# DAC_ADC_External.net
KiCad netlist of a schematic drawn in Altium Designer
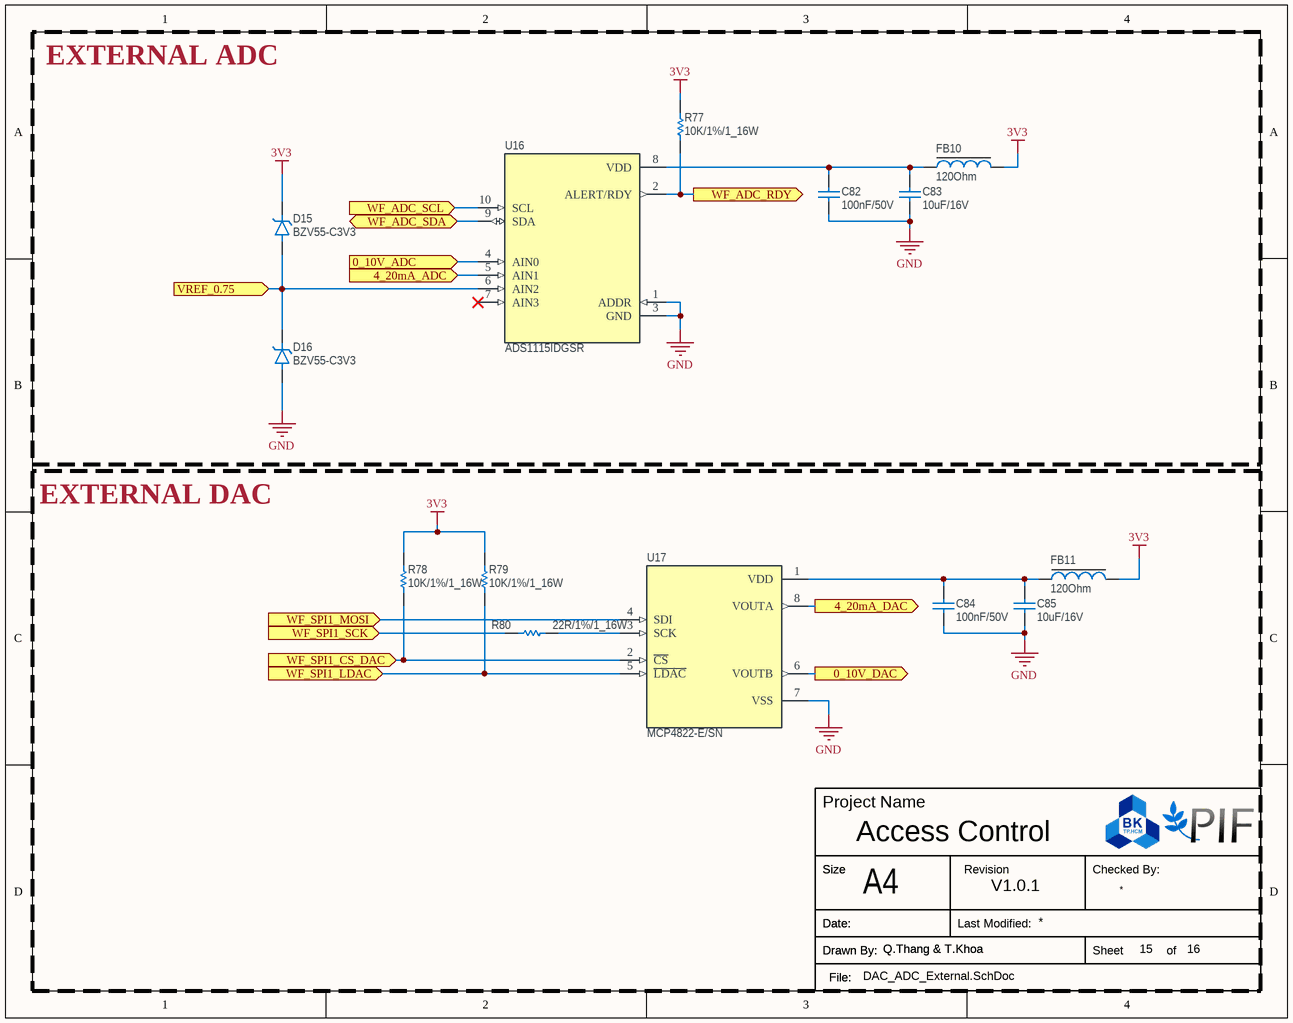
[diagram p0: DAC_ADC_External.SchDoc]

(export (version "E")
  (design (tool "Eeschema 10.0.6"))
  (components
    (comp (ref "C82")
      (value "100nF/50V")
      (footprint "CAP_0603")
      (description "CAP, size 0603, 100nF, 50V")
      (fields (field (name "SUPPLY PART NUMBER") "Tụ Gốm 0603 100nF (0.1uF) 50V"))
      (libsource (lib "BluetoothTracking") (part "Ceramic_Cap_100nF_50V_0603"))
    )
    (comp (ref "C83")
      (value "10uF/16V")
      (footprint "CAP_0603")
      (description "CAP, size 0603, 10uF, 16V")
      (fields (field (name "SUPPLY PART NUMBER") "Tụ Gốm 0603 10uF 16V"))
      (libsource (lib "BluetoothTracking") (part "Ceramic_Cap_10uF_16V_0603"))
    )
    (comp (ref "C84")
      (value "100nF/50V")
      (footprint "CAP_0603")
      (description "CAP, size 0603, 100nF, 50V")
      (fields (field (name "SUPPLY PART NUMBER") "Tụ Gốm 0603 100nF (0.1uF) 50V"))
      (libsource (lib "BluetoothTracking") (part "Ceramic_Cap_100nF_50V_0603"))
    )
    (comp (ref "C85")
      (value "10uF/16V")
      (footprint "CAP_0603")
      (description "CAP, size 0603, 10uF, 16V")
      (fields (field (name "SUPPLY PART NUMBER") "Tụ Gốm 0603 10uF 16V"))
      (libsource (lib "BluetoothTracking") (part "Ceramic_Cap_10uF_16V_0603"))
    )
    (comp (ref "D15")
      (value "BZV55-C3V3")
      (footprint "SOD-80")
      (description "DIODE ZENER 3.3V 500 mW")
      (libsource (lib "BluetoothTracking") (part "Diode_BZV55C3V3"))
    )
    (comp (ref "D16")
      (value "BZV55-C3V3")
      (footprint "SOD-80")
      (description "DIODE ZENER 3.3V 500 mW")
      (libsource (lib "BluetoothTracking") (part "Diode_BZV55C3V3"))
    )
    (comp (ref "FB10")
      (value "120Ohm")
      (footprint "Ferrite_Bead_0805")
      (description "Ferrite Bead, size 0805, 120Ohm, 2A")
      (fields (field (name "SUPPLY PART NUMBER") "CBW201209U121T Ferrite Beads 2A 120 Ohm 0805"))
      (libsource (lib "BluetoothTracking") (part "Ferrite_Bead_120Ohm_2A_0805"))
    )
    (comp (ref "FB11")
      (value "120Ohm")
      (footprint "Ferrite_Bead_0805")
      (description "Ferrite Bead, size 0805, 120Ohm, 2A")
      (fields (field (name "SUPPLY PART NUMBER") "CBW201209U121T Ferrite Beads 2A 120 Ohm 0805"))
      (libsource (lib "BluetoothTracking") (part "Ferrite_Bead_120Ohm_2A_0805"))
    )
    (comp (ref "R77")
      (value "10K/1%/1_16W")
      (footprint "RESISTOR_0402")
      (description "Resistor 0402 10KOhm 1% 1_16W")
      (fields (field (name "SUPPLY PART NUMBER") "Điện Trở 10 KOhm 0402 1%"))
      (libsource (lib "BluetoothTracking") (part "Res_10K_0402_1%"))
    )
    (comp (ref "R78")
      (value "10K/1%/1_16W")
      (footprint "RESISTOR_0402")
      (description "Resistor 0402 10KOhm 1% 1_16W")
      (fields (field (name "SUPPLY PART NUMBER") "Điện Trở 10 KOhm 0402 1%"))
      (libsource (lib "BluetoothTracking") (part "Res_10K_0402_1%"))
    )
    (comp (ref "R79")
      (value "10K/1%/1_16W")
      (footprint "RESISTOR_0402")
      (description "Resistor 0402 10KOhm 1% 1_16W")
      (fields (field (name "SUPPLY PART NUMBER") "Điện Trở 10 KOhm 0402 1%"))
      (libsource (lib "BluetoothTracking") (part "Res_10K_0402_1%"))
    )
    (comp (ref "R80")
      (value "22R/1%/1_16W")
      (footprint "RESISTOR_0402")
      (description "Resistor 0402 22 Ohm 1% 1_16W")
      (libsource (lib "BluetoothTracking") (part "Res_22R_0402_1%"))
    )
    (comp (ref "U16")
      (value "ADS1115IDGSR")
      (footprint "VSSOP-10")
      (fields (field (name "SUPPLY PART NUMBER") "ADS1115IDGSR IC ADC 16-Bit Sigma-Delta 10-VSSOP"))
      (libsource (lib "BluetoothTracking") (part "ADS1115IDGSR"))
    )
    (comp (ref "U17")
      (value "MCP4822-E/SN")
      (footprint "SOIC-8")
      (description "12 Bit Digital to Analog Converter 2 8-SOIC")
      (fields (field (name "SUPPLY PART NUMBER") "MCP4822-E/SN SOIC-8 DAC 12Bit Chính Hãng Microchip"))
      (libsource (lib "BluetoothTracking") (part "MCP4822-E/SN"))
    )
  )
  (nets
    (net (code "1") (name "/0_10V_ADC") (class "Default")
      (node (ref "U16") (pin "4") (pinfunction "AIN0_4") (pintype "input"))
    )
    (net (code "2") (name "/0_10V_DAC") (class "Default")
      (node (ref "U17") (pin "6") (pinfunction "VOUTB_6") (pintype "output"))
    )
    (net (code "3") (name "/4_20mA_ADC") (class "Default")
      (node (ref "U16") (pin "5") (pinfunction "AIN1_5") (pintype "input"))
    )
    (net (code "4") (name "/4_20mA_DAC") (class "Default")
      (node (ref "U17") (pin "8") (pinfunction "VOUTA_8") (pintype "output"))
    )
    (net (code "5") (name "/VREF_0.75") (class "Default")
      (node (ref "D15") (pin "A") (pinfunction "A_A") (pintype "passive"))
      (node (ref "D16") (pin "C") (pinfunction "C_C") (pintype "passive"))
      (node (ref "U16") (pin "6") (pinfunction "AIN2_6") (pintype "input"))
    )
    (net (code "6") (name "/WF_ADC_RDY") (class "Default")
      (node (ref "R77") (pin "1") (pinfunction "1_1") (pintype "passive"))
      (node (ref "U16") (pin "2") (pinfunction "ALERT/RDY_2") (pintype "output"))
    )
    (net (code "7") (name "/WF_ADC_SCL") (class "Default")
      (node (ref "U16") (pin "10") (pinfunction "SCL_10") (pintype "input"))
    )
    (net (code "8") (name "/WF_ADC_SDA") (class "Default")
      (node (ref "U16") (pin "9") (pinfunction "SDA_9") (pintype "bidirectional"))
    )
    (net (code "9") (name "/WF_SPI1_CS_DAC") (class "Default")
      (node (ref "R78") (pin "1") (pinfunction "1_1") (pintype "passive"))
      (node (ref "U17") (pin "2") (pinfunction "~{CS}_2") (pintype "input"))
    )
    (net (code "10") (name "/WF_SPI1_LDAC") (class "Default")
      (node (ref "R79") (pin "1") (pinfunction "1_1") (pintype "passive"))
      (node (ref "U17") (pin "5") (pinfunction "~{LDAC}_5") (pintype "input"))
    )
    (net (code "11") (name "/WF_SPI1_MOSI") (class "Default")
      (node (ref "U17") (pin "4") (pinfunction "SDI_4") (pintype "input"))
    )
    (net (code "12") (name "/WF_SPI1_SCK") (class "Default")
      (node (ref "R80") (pin "1") (pinfunction "1_1") (pintype "passive"))
    )
    (net (code "13") (name "3V3") (class "Default")
      (node (ref "D15") (pin "C") (pinfunction "C_C") (pintype "passive"))
      (node (ref "FB10") (pin "2") (pinfunction "2_2") (pintype "passive"))
      (node (ref "FB11") (pin "2") (pinfunction "2_2") (pintype "passive"))
      (node (ref "R77") (pin "2") (pinfunction "2_2") (pintype "passive"))
      (node (ref "R78") (pin "2") (pinfunction "2_2") (pintype "passive"))
      (node (ref "R79") (pin "2") (pinfunction "2_2") (pintype "passive"))
    )
    (net (code "14") (name "GND") (class "Default")
      (node (ref "C82") (pin "1") (pinfunction "1_1") (pintype "passive"))
      (node (ref "C83") (pin "1") (pinfunction "1_1") (pintype "passive"))
      (node (ref "C84") (pin "1") (pinfunction "1_1") (pintype "passive"))
      (node (ref "C85") (pin "1") (pinfunction "1_1") (pintype "passive"))
      (node (ref "D16") (pin "A") (pinfunction "A_A") (pintype "passive"))
      (node (ref "U16") (pin "1") (pinfunction "ADDR_1") (pintype "input"))
      (node (ref "U16") (pin "3") (pinfunction "GND_3") (pintype "power_in"))
      (node (ref "U17") (pin "7") (pinfunction "VSS_7") (pintype "power_in"))
    )
    (net (code "15") (name "Net-(U16-VDD)") (class "Default")
      (node (ref "C82") (pin "2") (pinfunction "2_2") (pintype "passive"))
      (node (ref "C83") (pin "2") (pinfunction "2_2") (pintype "passive"))
      (node (ref "FB10") (pin "1") (pinfunction "1_1") (pintype "passive"))
      (node (ref "U16") (pin "8") (pinfunction "VDD_8") (pintype "power_in"))
    )
    (net (code "16") (name "Net-(U17-SCK)") (class "Default")
      (node (ref "R80") (pin "2") (pinfunction "2_2") (pintype "passive"))
      (node (ref "U17") (pin "3") (pinfunction "SCK_3") (pintype "input"))
    )
    (net (code "17") (name "Net-(U17-VDD)") (class "Default")
      (node (ref "C84") (pin "2") (pinfunction "2_2") (pintype "passive"))
      (node (ref "C85") (pin "2") (pinfunction "2_2") (pintype "passive"))
      (node (ref "FB11") (pin "1") (pinfunction "1_1") (pintype "passive"))
      (node (ref "U17") (pin "1") (pinfunction "VDD_1") (pintype "power_in"))
    )
    (net (code "18") (name "unconnected-(U16-AIN3-Pad7)") (class "Default")
      (node (ref "U16") (pin "7") (pinfunction "AIN3_7") (pintype "input+no_connect"))
    )
  )
)
